# Esquema_Eletrico_Eagle.net
KiCad netlist of a schematic drawn in EAGLE
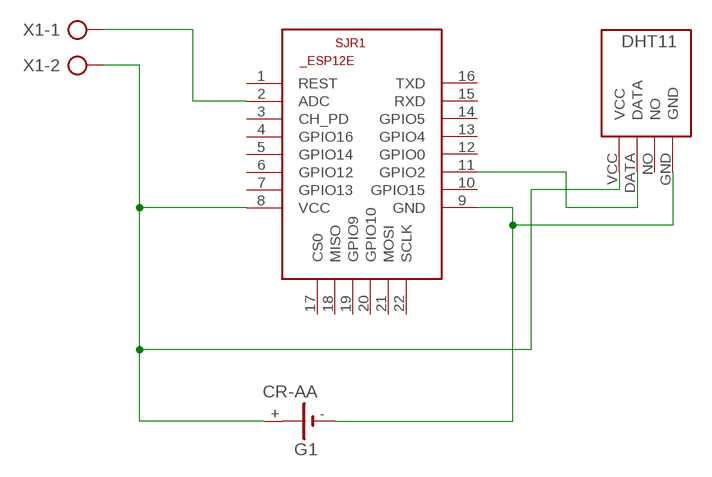
[diagram p0: schematic, sheet 1]

(export (version "E")
  (design (tool "Eeschema 10.0.6"))
  (components
    (comp (ref "G1")
      (value "CR-AA")
      (footprint "eagle-import:CRAA")
      (libsource (lib "eagle-import") (part "CR-AA"))
    )
    (comp (ref "SJR1")
      (value "ESP8266-12EESP12E")
      (footprint "eagle-import:ESP8266-ESP12E")
      (libsource (lib "eagle-import") (part "ESP8266-12EESP12E"))
    )
    (comp (ref "U$1")
      (value "DHT11-PION.")
      (footprint "eagle-import:DHT11-PION.")
      (libsource (lib "eagle-import") (part "DHT11-PION."))
    )
    (comp (ref "X1")
      (value "AK300/2")
      (footprint "eagle-import:AK300_2")
      (libsource (lib "eagle-import") (part "AK300/2"))
    )
  )
  (nets
    (net (code "1") (name "Net-(SJR1-ADC)") (class "Default")
      (node (ref "SJR1") (pin "2") (pinfunction "ADC_2") (pintype "bidirectional"))
      (node (ref "X1") (pin "1") (pinfunction "KL_1") (pintype "passive"))
    )
    (net (code "2") (name "Net-(SJR1-GND)") (class "Default")
      (node (ref "G1") (pin "-") (pinfunction "-_-") (pintype "passive"))
      (node (ref "SJR1") (pin "9") (pinfunction "GND_9") (pintype "bidirectional"))
      (node (ref "U$1") (pin "GND") (pinfunction "GND_GND") (pintype "bidirectional"))
    )
    (net (code "3") (name "Net-(SJR1-GPIO2)") (class "Default")
      (node (ref "SJR1") (pin "11") (pinfunction "GPIO2_11") (pintype "bidirectional"))
      (node (ref "U$1") (pin "DATA") (pinfunction "DATA_DATA") (pintype "bidirectional"))
    )
    (net (code "4") (name "Net-(SJR1-VCC)") (class "Default")
      (node (ref "G1") (pin "+") (pinfunction "+_+") (pintype "passive"))
      (node (ref "SJR1") (pin "8") (pinfunction "VCC_8") (pintype "bidirectional"))
      (node (ref "U$1") (pin "VCC") (pinfunction "VCC_VCC") (pintype "bidirectional"))
      (node (ref "X1") (pin "2") (pinfunction "KL_2") (pintype "passive"))
    )
    (net (code "5") (name "unconnected-(G1-+-Pad+@1)") (class "Default")
      (node (ref "G1") (pin "+@1") (pinfunction "+_+@1") (pintype "passive"))
    )
    (net (code "6") (name "unconnected-(SJR1-CH_PD-Pad3)") (class "Default")
      (node (ref "SJR1") (pin "3") (pinfunction "CH_PD_3") (pintype "bidirectional"))
    )
    (net (code "7") (name "unconnected-(SJR1-CS0-Pad17)") (class "Default")
      (node (ref "SJR1") (pin "17") (pinfunction "CS0_17") (pintype "bidirectional"))
    )
    (net (code "8") (name "unconnected-(SJR1-GPIO0-Pad12)") (class "Default")
      (node (ref "SJR1") (pin "12") (pinfunction "GPIO0_12") (pintype "bidirectional"))
    )
    (net (code "9") (name "unconnected-(SJR1-GPIO4-Pad13)") (class "Default")
      (node (ref "SJR1") (pin "13") (pinfunction "GPIO4_13") (pintype "bidirectional"))
    )
    (net (code "10") (name "unconnected-(SJR1-GPIO5-Pad14)") (class "Default")
      (node (ref "SJR1") (pin "14") (pinfunction "GPIO5_14") (pintype "bidirectional"))
    )
    (net (code "11") (name "unconnected-(SJR1-GPIO9-Pad19)") (class "Default")
      (node (ref "SJR1") (pin "19") (pinfunction "GPIO9_19") (pintype "bidirectional"))
    )
    (net (code "12") (name "unconnected-(SJR1-GPIO10-Pad20)") (class "Default")
      (node (ref "SJR1") (pin "20") (pinfunction "GPIO10_20") (pintype "bidirectional"))
    )
    (net (code "13") (name "unconnected-(SJR1-GPIO12-Pad6)") (class "Default")
      (node (ref "SJR1") (pin "6") (pinfunction "GPIO12_6") (pintype "bidirectional"))
    )
    (net (code "14") (name "unconnected-(SJR1-GPIO13-Pad7)") (class "Default")
      (node (ref "SJR1") (pin "7") (pinfunction "GPIO13_7") (pintype "bidirectional"))
    )
    (net (code "15") (name "unconnected-(SJR1-GPIO14-Pad5)") (class "Default")
      (node (ref "SJR1") (pin "5") (pinfunction "GPIO14_5") (pintype "bidirectional"))
    )
    (net (code "16") (name "unconnected-(SJR1-GPIO15-Pad10)") (class "Default")
      (node (ref "SJR1") (pin "10") (pinfunction "GPIO15_10") (pintype "bidirectional"))
    )
    (net (code "17") (name "unconnected-(SJR1-GPIO16-Pad4)") (class "Default")
      (node (ref "SJR1") (pin "4") (pinfunction "GPIO16_4") (pintype "bidirectional"))
    )
    (net (code "18") (name "unconnected-(SJR1-MISO-Pad18)") (class "Default")
      (node (ref "SJR1") (pin "18") (pinfunction "MISO_18") (pintype "bidirectional"))
    )
    (net (code "19") (name "unconnected-(SJR1-MOSI-Pad21)") (class "Default")
      (node (ref "SJR1") (pin "21") (pinfunction "MOSI_21") (pintype "bidirectional"))
    )
    (net (code "20") (name "unconnected-(SJR1-REST-Pad1)") (class "Default")
      (node (ref "SJR1") (pin "1") (pinfunction "REST_1") (pintype "bidirectional"))
    )
    (net (code "21") (name "unconnected-(SJR1-RXD-Pad15)") (class "Default")
      (node (ref "SJR1") (pin "15") (pinfunction "RXD_15") (pintype "bidirectional"))
    )
    (net (code "22") (name "unconnected-(SJR1-SCLK-Pad22)") (class "Default")
      (node (ref "SJR1") (pin "22") (pinfunction "SCLK_22") (pintype "bidirectional"))
    )
    (net (code "23") (name "unconnected-(SJR1-TXD-Pad16)") (class "Default")
      (node (ref "SJR1") (pin "16") (pinfunction "TXD_16") (pintype "bidirectional"))
    )
    (net (code "24") (name "unconnected-(U$1-PadNO)") (class "Default")
      (node (ref "U$1") (pin "NO") (pinfunction "NO_NO") (pintype "bidirectional"))
    )
  )
)
